# MinimalDigitalAmp.net
KiCad netlist of a schematic drawn in EAGLE
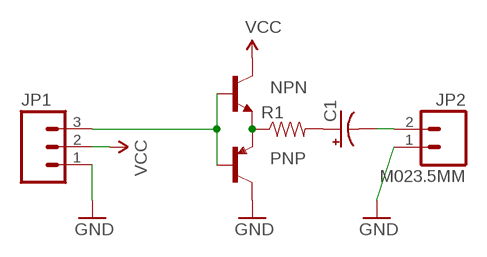
[diagram p0: schematic, sheet 1]

(export (version "E")
  (design (tool "Eeschema 10.0.6"))
  (components
    (comp (ref "C1")
      (value "CAP_POLPTH1")
      (footprint "eagle-import:CPOL-RADIAL-100UF-25V")
      (libsource (lib "eagle-import") (part "CAP_POLPTH1"))
    )
    (comp (ref "JP1")
      (value "M03PTH")
      (footprint "eagle-import:1X03")
      (libsource (lib "eagle-import") (part "M03PTH"))
    )
    (comp (ref "JP2")
      (value "M023.5MM")
      (footprint "eagle-import:SCREWTERMINAL-3.5MM-2")
      (libsource (lib "eagle-import") (part "M023.5MM"))
    )
    (comp (ref "NPN")
      (value "TRANSISTOR_NPNTO-92-AMMO")
      (footprint "eagle-import:TO-92-AMMO")
      (libsource (lib "eagle-import") (part "TRANSISTOR_NPNTO-92-AMMO"))
    )
    (comp (ref "PNP")
      (value "TRANSISTOR_PNPAMMO")
      (footprint "eagle-import:TO-92-AMMO")
      (libsource (lib "eagle-import") (part "TRANSISTOR_PNPAMMO"))
    )
    (comp (ref "R1")
      (value "RESISTORAXIAL-0.3")
      (footprint "eagle-import:AXIAL-0.3")
      (libsource (lib "eagle-import") (part "RESISTORAXIAL-0.3"))
    )
  )
  (nets
    (net (code "1") (name "GND") (class "Default")
      (node (ref "JP1") (pin "1") (pinfunction "1_1") (pintype "passive"))
      (node (ref "JP2") (pin "1") (pinfunction "1_1") (pintype "passive"))
      (node (ref "PNP") (pin "3") (pinfunction "C_3") (pintype "passive"))
    )
    (net (code "2") (name "Net-(C1-+)") (class "Default")
      (node (ref "C1") (pin "1") (pinfunction "+_1") (pintype "passive"))
      (node (ref "R1") (pin "P$2") (pinfunction "2_P$2") (pintype "passive"))
    )
    (net (code "3") (name "Net-(C1--)") (class "Default")
      (node (ref "C1") (pin "2") (pinfunction "-_2") (pintype "passive"))
      (node (ref "JP2") (pin "2") (pinfunction "2_2") (pintype "passive"))
    )
    (net (code "4") (name "Net-(NPN-B)") (class "Default")
      (node (ref "JP1") (pin "3") (pinfunction "3_3") (pintype "passive"))
      (node (ref "NPN") (pin "2") (pinfunction "B_2") (pintype "passive"))
      (node (ref "PNP") (pin "2") (pinfunction "B_2") (pintype "passive"))
    )
    (net (code "5") (name "Net-(NPN-E)") (class "Default")
      (node (ref "NPN") (pin "1") (pinfunction "E_1") (pintype "passive"))
      (node (ref "PNP") (pin "1") (pinfunction "E_1") (pintype "passive"))
      (node (ref "R1") (pin "P$1") (pinfunction "1_P$1") (pintype "passive"))
    )
    (net (code "6") (name "VCC") (class "Default")
      (node (ref "JP1") (pin "2") (pinfunction "2_2") (pintype "passive"))
      (node (ref "NPN") (pin "3") (pinfunction "C_3") (pintype "passive"))
    )
  )
)
